# 32pinromtoflash_-_piggyback_28pin.net
KiCad netlist of a schematic drawn in EAGLE
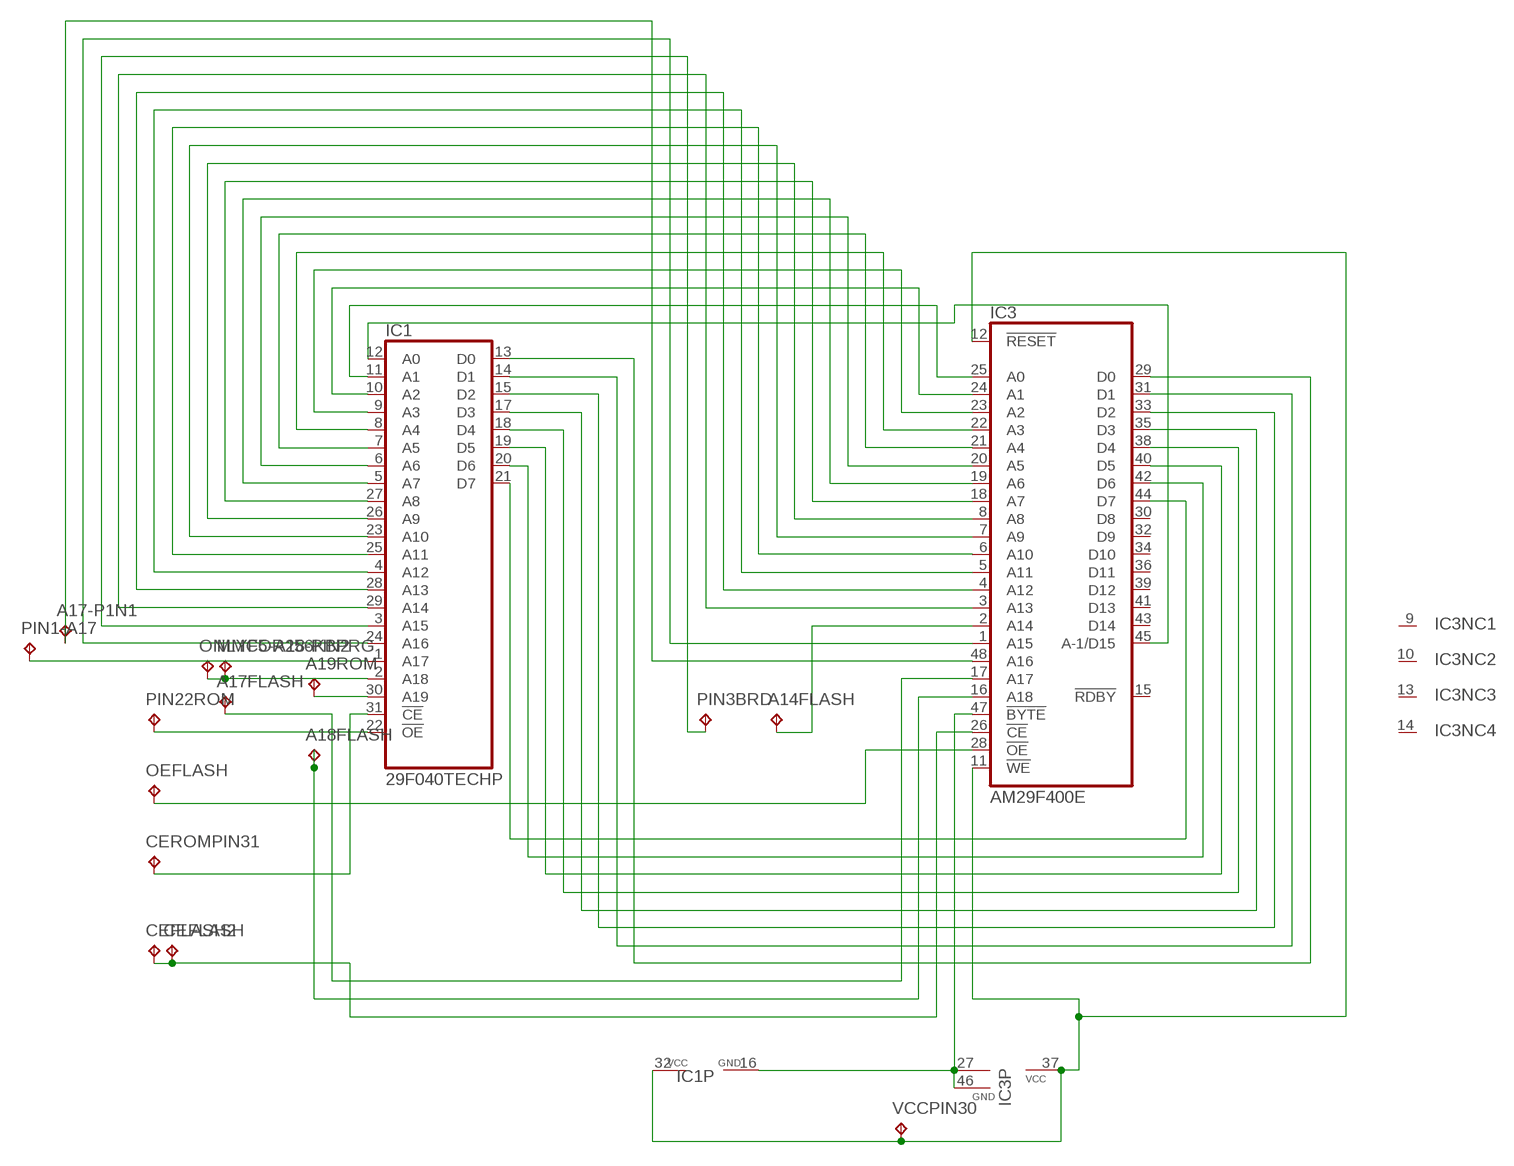
[diagram p0: schematic, sheet 1]

(export (version "E")
  (design (tool "Eeschema 10.0.6"))
  (components
    (comp (ref "A14FLASH")
      (value "TPTP07SQ")
      (footprint "eagle-import:TP07SQ")
      (libsource (lib "eagle-import") (part "TPTP07SQ"))
    )
    (comp (ref "A17-P1N1")
      (value "TPTP07SQ")
      (footprint "eagle-import:TP07SQ")
      (libsource (lib "eagle-import") (part "TPTP07SQ"))
    )
    (comp (ref "A17FLASH")
      (value "TPTP07SQ")
      (footprint "eagle-import:TP07SQ")
      (libsource (lib "eagle-import") (part "TPTP07SQ"))
    )
    (comp (ref "A18FLASH")
      (value "TPTP07SQ")
      (footprint "eagle-import:TP07SQ")
      (libsource (lib "eagle-import") (part "TPTP07SQ"))
    )
    (comp (ref "A19ROM")
      (value "TPTP07SQ")
      (footprint "eagle-import:TP07SQ")
      (libsource (lib "eagle-import") (part "TPTP07SQ"))
    )
    (comp (ref "CEFLASH")
      (value "TPTP07SQ")
      (footprint "eagle-import:TP07SQ")
      (libsource (lib "eagle-import") (part "TPTP07SQ"))
    )
    (comp (ref "CEFLASH2")
      (value "TPTP07SQ")
      (footprint "eagle-import:TP07SQ")
      (libsource (lib "eagle-import") (part "TPTP07SQ"))
    )
    (comp (ref "CEROMPIN31")
      (value "TPTP07SQ")
      (footprint "eagle-import:TP07SQ")
      (libsource (lib "eagle-import") (part "TPTP07SQ"))
    )
    (comp (ref "IC1")
      (value "29F040TECHP")
      (footprint "eagle-import:DIL32-3")
      (libsource (lib "eagle-import") (part "29F040PTECH"))
    )
    (comp (ref "IC3")
      (value "AM29F400E")
      (footprint "eagle-import:TSOP48")
      (libsource (lib "eagle-import") (part "AM29F400E"))
    )
    (comp (ref "MMC5-A18-PIN2")
      (value "TPTP07SQ")
      (footprint "eagle-import:TP07SQ")
      (libsource (lib "eagle-import") (part "TPTP07SQ"))
    )
    (comp (ref "OEFLASH")
      (value "TPTP07SQ")
      (footprint "eagle-import:TP07SQ")
      (libsource (lib "eagle-import") (part "TPTP07SQ"))
    )
    (comp (ref "ONLYFOR256KBPRG")
      (value "TPTP07SQ")
      (footprint "eagle-import:TP07SQ")
      (libsource (lib "eagle-import") (part "TPTP07SQ"))
    )
    (comp (ref "PIN1-A17")
      (value "TPTP07SQ")
      (footprint "eagle-import:TP07SQ")
      (libsource (lib "eagle-import") (part "TPTP07SQ"))
    )
    (comp (ref "PIN3BRD")
      (value "TPTP07SQ")
      (footprint "eagle-import:TP07SQ")
      (libsource (lib "eagle-import") (part "TPTP07SQ"))
    )
    (comp (ref "PIN22ROM")
      (value "TPTP07SQ")
      (footprint "eagle-import:TP07SQ")
      (libsource (lib "eagle-import") (part "TPTP07SQ"))
    )
    (comp (ref "VCCPIN30")
      (value "TPTP07SQ")
      (footprint "eagle-import:TP07SQ")
      (libsource (lib "eagle-import") (part "TPTP07SQ"))
    )
  )
  (nets
    (net (code "1") (name "Net-(IC1A-A0)") (class "Default")
      (node (ref "IC1") (pin "12") (pinfunction "A0_12") (pintype "input"))
      (node (ref "IC3") (pin "45") (pinfunction "A-1/D15_45") (pintype "tri_state"))
    )
    (net (code "2") (name "Net-(IC1A-A1)") (class "Default")
      (node (ref "IC1") (pin "11") (pinfunction "A1_11") (pintype "input"))
      (node (ref "IC3") (pin "25") (pinfunction "A0_25") (pintype "input"))
    )
    (net (code "3") (name "Net-(IC1A-A2)") (class "Default")
      (node (ref "IC1") (pin "10") (pinfunction "A2_10") (pintype "input"))
      (node (ref "IC3") (pin "24") (pinfunction "A1_24") (pintype "input"))
    )
    (net (code "4") (name "Net-(IC1A-A3)") (class "Default")
      (node (ref "IC1") (pin "9") (pinfunction "A3_9") (pintype "input"))
      (node (ref "IC3") (pin "23") (pinfunction "A2_23") (pintype "input"))
    )
    (net (code "5") (name "Net-(IC1A-A4)") (class "Default")
      (node (ref "IC1") (pin "8") (pinfunction "A4_8") (pintype "input"))
      (node (ref "IC3") (pin "22") (pinfunction "A3_22") (pintype "input"))
    )
    (net (code "6") (name "Net-(IC1A-A5)") (class "Default")
      (node (ref "IC1") (pin "7") (pinfunction "A5_7") (pintype "input"))
      (node (ref "IC3") (pin "21") (pinfunction "A4_21") (pintype "input"))
    )
    (net (code "7") (name "Net-(IC1A-A6)") (class "Default")
      (node (ref "IC1") (pin "6") (pinfunction "A6_6") (pintype "input"))
      (node (ref "IC3") (pin "20") (pinfunction "A5_20") (pintype "input"))
    )
    (net (code "8") (name "Net-(IC1A-A7)") (class "Default")
      (node (ref "IC1") (pin "5") (pinfunction "A7_5") (pintype "input"))
      (node (ref "IC3") (pin "19") (pinfunction "A6_19") (pintype "input"))
    )
    (net (code "9") (name "Net-(IC1A-A8)") (class "Default")
      (node (ref "IC1") (pin "27") (pinfunction "A8_27") (pintype "input"))
      (node (ref "IC3") (pin "18") (pinfunction "A7_18") (pintype "input"))
    )
    (net (code "10") (name "Net-(IC1A-A9)") (class "Default")
      (node (ref "IC1") (pin "26") (pinfunction "A9_26") (pintype "input"))
      (node (ref "IC3") (pin "8") (pinfunction "A8_8") (pintype "input"))
    )
    (net (code "11") (name "Net-(IC1A-A10)") (class "Default")
      (node (ref "IC1") (pin "23") (pinfunction "A10_23") (pintype "input"))
      (node (ref "IC3") (pin "7") (pinfunction "A9_7") (pintype "input"))
    )
    (net (code "12") (name "Net-(IC1A-A11)") (class "Default")
      (node (ref "IC1") (pin "25") (pinfunction "A11_25") (pintype "input"))
      (node (ref "IC3") (pin "6") (pinfunction "A10_6") (pintype "input"))
    )
    (net (code "13") (name "Net-(IC1A-A12)") (class "Default")
      (node (ref "IC1") (pin "4") (pinfunction "A12_4") (pintype "input"))
      (node (ref "IC3") (pin "5") (pinfunction "A11_5") (pintype "input"))
    )
    (net (code "14") (name "Net-(IC1A-A13)") (class "Default")
      (node (ref "IC1") (pin "28") (pinfunction "A13_28") (pintype "input"))
      (node (ref "IC3") (pin "4") (pinfunction "A12_4") (pintype "input"))
    )
    (net (code "15") (name "Net-(IC1A-A14)") (class "Default")
      (node (ref "IC1") (pin "29") (pinfunction "A14_29") (pintype "input"))
      (node (ref "IC3") (pin "3") (pinfunction "A13_3") (pintype "input"))
    )
    (net (code "16") (name "Net-(IC1A-A15)") (class "Default")
      (node (ref "IC1") (pin "3") (pinfunction "A15_3") (pintype "input"))
      (node (ref "PIN3BRD") (pin "TP") (pinfunction "TP_TP") (pintype "input"))
    )
    (net (code "17") (name "Net-(IC1A-A16)") (class "Default")
      (node (ref "IC1") (pin "24") (pinfunction "A16_24") (pintype "input"))
      (node (ref "IC3") (pin "1") (pinfunction "A15_1") (pintype "input"))
    )
    (net (code "18") (name "Net-(IC1A-A17)") (class "Default")
      (node (ref "IC1") (pin "1") (pinfunction "A17_1") (pintype "input"))
      (node (ref "PIN1-A17") (pin "TP") (pinfunction "TP_TP") (pintype "input"))
    )
    (net (code "19") (name "Net-(IC1A-A18)") (class "Default")
      (node (ref "IC1") (pin "2") (pinfunction "A18_2") (pintype "input"))
      (node (ref "MMC5-A18-PIN2") (pin "TP") (pinfunction "TP_TP") (pintype "input"))
      (node (ref "ONLYFOR256KBPRG") (pin "TP") (pinfunction "TP_TP") (pintype "input"))
    )
    (net (code "20") (name "Net-(IC1A-A19)") (class "Default")
      (node (ref "A19ROM") (pin "TP") (pinfunction "TP_TP") (pintype "input"))
      (node (ref "IC1") (pin "30") (pinfunction "A19_30") (pintype "input"))
    )
    (net (code "21") (name "Net-(IC1A-D0)") (class "Default")
      (node (ref "IC1") (pin "13") (pinfunction "D0_13") (pintype "tri_state"))
      (node (ref "IC3") (pin "29") (pinfunction "D0_29") (pintype "tri_state"))
    )
    (net (code "22") (name "Net-(IC1A-D1)") (class "Default")
      (node (ref "IC1") (pin "14") (pinfunction "D1_14") (pintype "tri_state"))
      (node (ref "IC3") (pin "31") (pinfunction "D1_31") (pintype "tri_state"))
    )
    (net (code "23") (name "Net-(IC1A-D2)") (class "Default")
      (node (ref "IC1") (pin "15") (pinfunction "D2_15") (pintype "tri_state"))
      (node (ref "IC3") (pin "33") (pinfunction "D2_33") (pintype "tri_state"))
    )
    (net (code "24") (name "Net-(IC1A-D3)") (class "Default")
      (node (ref "IC1") (pin "17") (pinfunction "D3_17") (pintype "tri_state"))
      (node (ref "IC3") (pin "35") (pinfunction "D3_35") (pintype "tri_state"))
    )
    (net (code "25") (name "Net-(IC1A-D4)") (class "Default")
      (node (ref "IC1") (pin "18") (pinfunction "D4_18") (pintype "tri_state"))
      (node (ref "IC3") (pin "38") (pinfunction "D4_38") (pintype "tri_state"))
    )
    (net (code "26") (name "Net-(IC1A-D5)") (class "Default")
      (node (ref "IC1") (pin "19") (pinfunction "D5_19") (pintype "tri_state"))
      (node (ref "IC3") (pin "40") (pinfunction "D5_40") (pintype "tri_state"))
    )
    (net (code "27") (name "Net-(IC1A-D6)") (class "Default")
      (node (ref "IC1") (pin "20") (pinfunction "D6_20") (pintype "tri_state"))
      (node (ref "IC3") (pin "42") (pinfunction "D6_42") (pintype "tri_state"))
    )
    (net (code "28") (name "Net-(IC1A-D7)") (class "Default")
      (node (ref "IC1") (pin "21") (pinfunction "D7_21") (pintype "input"))
      (node (ref "IC3") (pin "44") (pinfunction "D7_44") (pintype "tri_state"))
    )
    (net (code "29") (name "Net-(IC1A-~{CE})") (class "Default")
      (node (ref "CEROMPIN31") (pin "TP") (pinfunction "TP_TP") (pintype "input"))
      (node (ref "IC1") (pin "31") (pinfunction "~{CE}_31") (pintype "input"))
    )
    (net (code "30") (name "Net-(IC1A-~{OE})") (class "Default")
      (node (ref "IC1") (pin "22") (pinfunction "~{OE}_22") (pintype "input"))
      (node (ref "PIN22ROM") (pin "TP") (pinfunction "TP_TP") (pintype "input"))
    )
    (net (code "31") (name "Net-(IC1B-GND)") (class "Default")
      (node (ref "IC1") (pin "16") (pinfunction "GND_16") (pintype "power_in"))
      (node (ref "IC3") (pin "27") (pinfunction "GND_27") (pintype "power_in"))
      (node (ref "IC3") (pin "46") (pinfunction "GND_46") (pintype "power_in"))
      (node (ref "IC3") (pin "47") (pinfunction "~{BYTE}_47") (pintype "input"))
    )
    (net (code "32") (name "Net-(IC1B-VCC)") (class "Default")
      (node (ref "IC1") (pin "32") (pinfunction "VCC_32") (pintype "power_in"))
      (node (ref "IC3") (pin "11") (pinfunction "~{WE}_11") (pintype "input"))
      (node (ref "IC3") (pin "12") (pinfunction "~{RESET}_12") (pintype "input"))
      (node (ref "IC3") (pin "37") (pinfunction "VCC_37") (pintype "power_in"))
      (node (ref "VCCPIN30") (pin "TP") (pinfunction "TP_TP") (pintype "input"))
    )
    (net (code "33") (name "Net-(IC3A-A14)") (class "Default")
      (node (ref "A14FLASH") (pin "TP") (pinfunction "TP_TP") (pintype "input"))
      (node (ref "IC3") (pin "2") (pinfunction "A14_2") (pintype "input"))
    )
    (net (code "34") (name "Net-(IC3A-A16)") (class "Default")
      (node (ref "A17-P1N1") (pin "TP") (pinfunction "TP_TP") (pintype "input"))
      (node (ref "IC3") (pin "48") (pinfunction "A16_48") (pintype "input"))
    )
    (net (code "35") (name "Net-(IC3A-A17)") (class "Default")
      (node (ref "A17FLASH") (pin "TP") (pinfunction "TP_TP") (pintype "input"))
      (node (ref "IC3") (pin "17") (pinfunction "A17_17") (pintype "input"))
    )
    (net (code "36") (name "Net-(IC3A-A18)") (class "Default")
      (node (ref "A18FLASH") (pin "TP") (pinfunction "TP_TP") (pintype "input"))
      (node (ref "IC3") (pin "16") (pinfunction "A18_16") (pintype "input"))
    )
    (net (code "37") (name "Net-(IC3A-~{CE})") (class "Default")
      (node (ref "CEFLASH") (pin "TP") (pinfunction "TP_TP") (pintype "input"))
      (node (ref "CEFLASH2") (pin "TP") (pinfunction "TP_TP") (pintype "input"))
      (node (ref "IC3") (pin "26") (pinfunction "~{CE}_26") (pintype "input"))
    )
    (net (code "38") (name "Net-(IC3A-~{OE})") (class "Default")
      (node (ref "IC3") (pin "28") (pinfunction "~{OE}_28") (pintype "input"))
      (node (ref "OEFLASH") (pin "TP") (pinfunction "TP_TP") (pintype "input"))
    )
    (net (code "39") (name "unconnected-(IC3A-D8-Pad30)") (class "Default")
      (node (ref "IC3") (pin "30") (pinfunction "D8_30") (pintype "tri_state"))
    )
    (net (code "40") (name "unconnected-(IC3A-D9-Pad32)") (class "Default")
      (node (ref "IC3") (pin "32") (pinfunction "D9_32") (pintype "tri_state"))
    )
    (net (code "41") (name "unconnected-(IC3A-D10-Pad34)") (class "Default")
      (node (ref "IC3") (pin "34") (pinfunction "D10_34") (pintype "tri_state"))
    )
    (net (code "42") (name "unconnected-(IC3A-D11-Pad36)") (class "Default")
      (node (ref "IC3") (pin "36") (pinfunction "D11_36") (pintype "tri_state"))
    )
    (net (code "43") (name "unconnected-(IC3A-D12-Pad39)") (class "Default")
      (node (ref "IC3") (pin "39") (pinfunction "D12_39") (pintype "tri_state"))
    )
    (net (code "44") (name "unconnected-(IC3A-D13-Pad41)") (class "Default")
      (node (ref "IC3") (pin "41") (pinfunction "D13_41") (pintype "tri_state"))
    )
    (net (code "45") (name "unconnected-(IC3A-D14-Pad43)") (class "Default")
      (node (ref "IC3") (pin "43") (pinfunction "D14_43") (pintype "tri_state"))
    )
    (net (code "46") (name "unconnected-(IC3A-~{RDBY}-Pad15)") (class "Default")
      (node (ref "IC3") (pin "15") (pinfunction "~{RDBY}_15") (pintype "output"))
    )
    (net (code "47") (name "unconnected-(IC3B-NC-Pad9)") (class "Default")
      (node (ref "IC3") (pin "9") (pinfunction "NC_9") (pintype "no_connect"))
    )
    (net (code "48") (name "unconnected-(IC3C-NC-Pad10)") (class "Default")
      (node (ref "IC3") (pin "10") (pinfunction "NC_10") (pintype "no_connect"))
    )
    (net (code "49") (name "unconnected-(IC3D-NC-Pad13)") (class "Default")
      (node (ref "IC3") (pin "13") (pinfunction "NC_13") (pintype "no_connect"))
    )
    (net (code "50") (name "unconnected-(IC3E-NC-Pad14)") (class "Default")
      (node (ref "IC3") (pin "14") (pinfunction "NC_14") (pintype "no_connect"))
    )
  )
)
